# DL0815.net
KiCad netlist of a schematic drawn in EAGLE
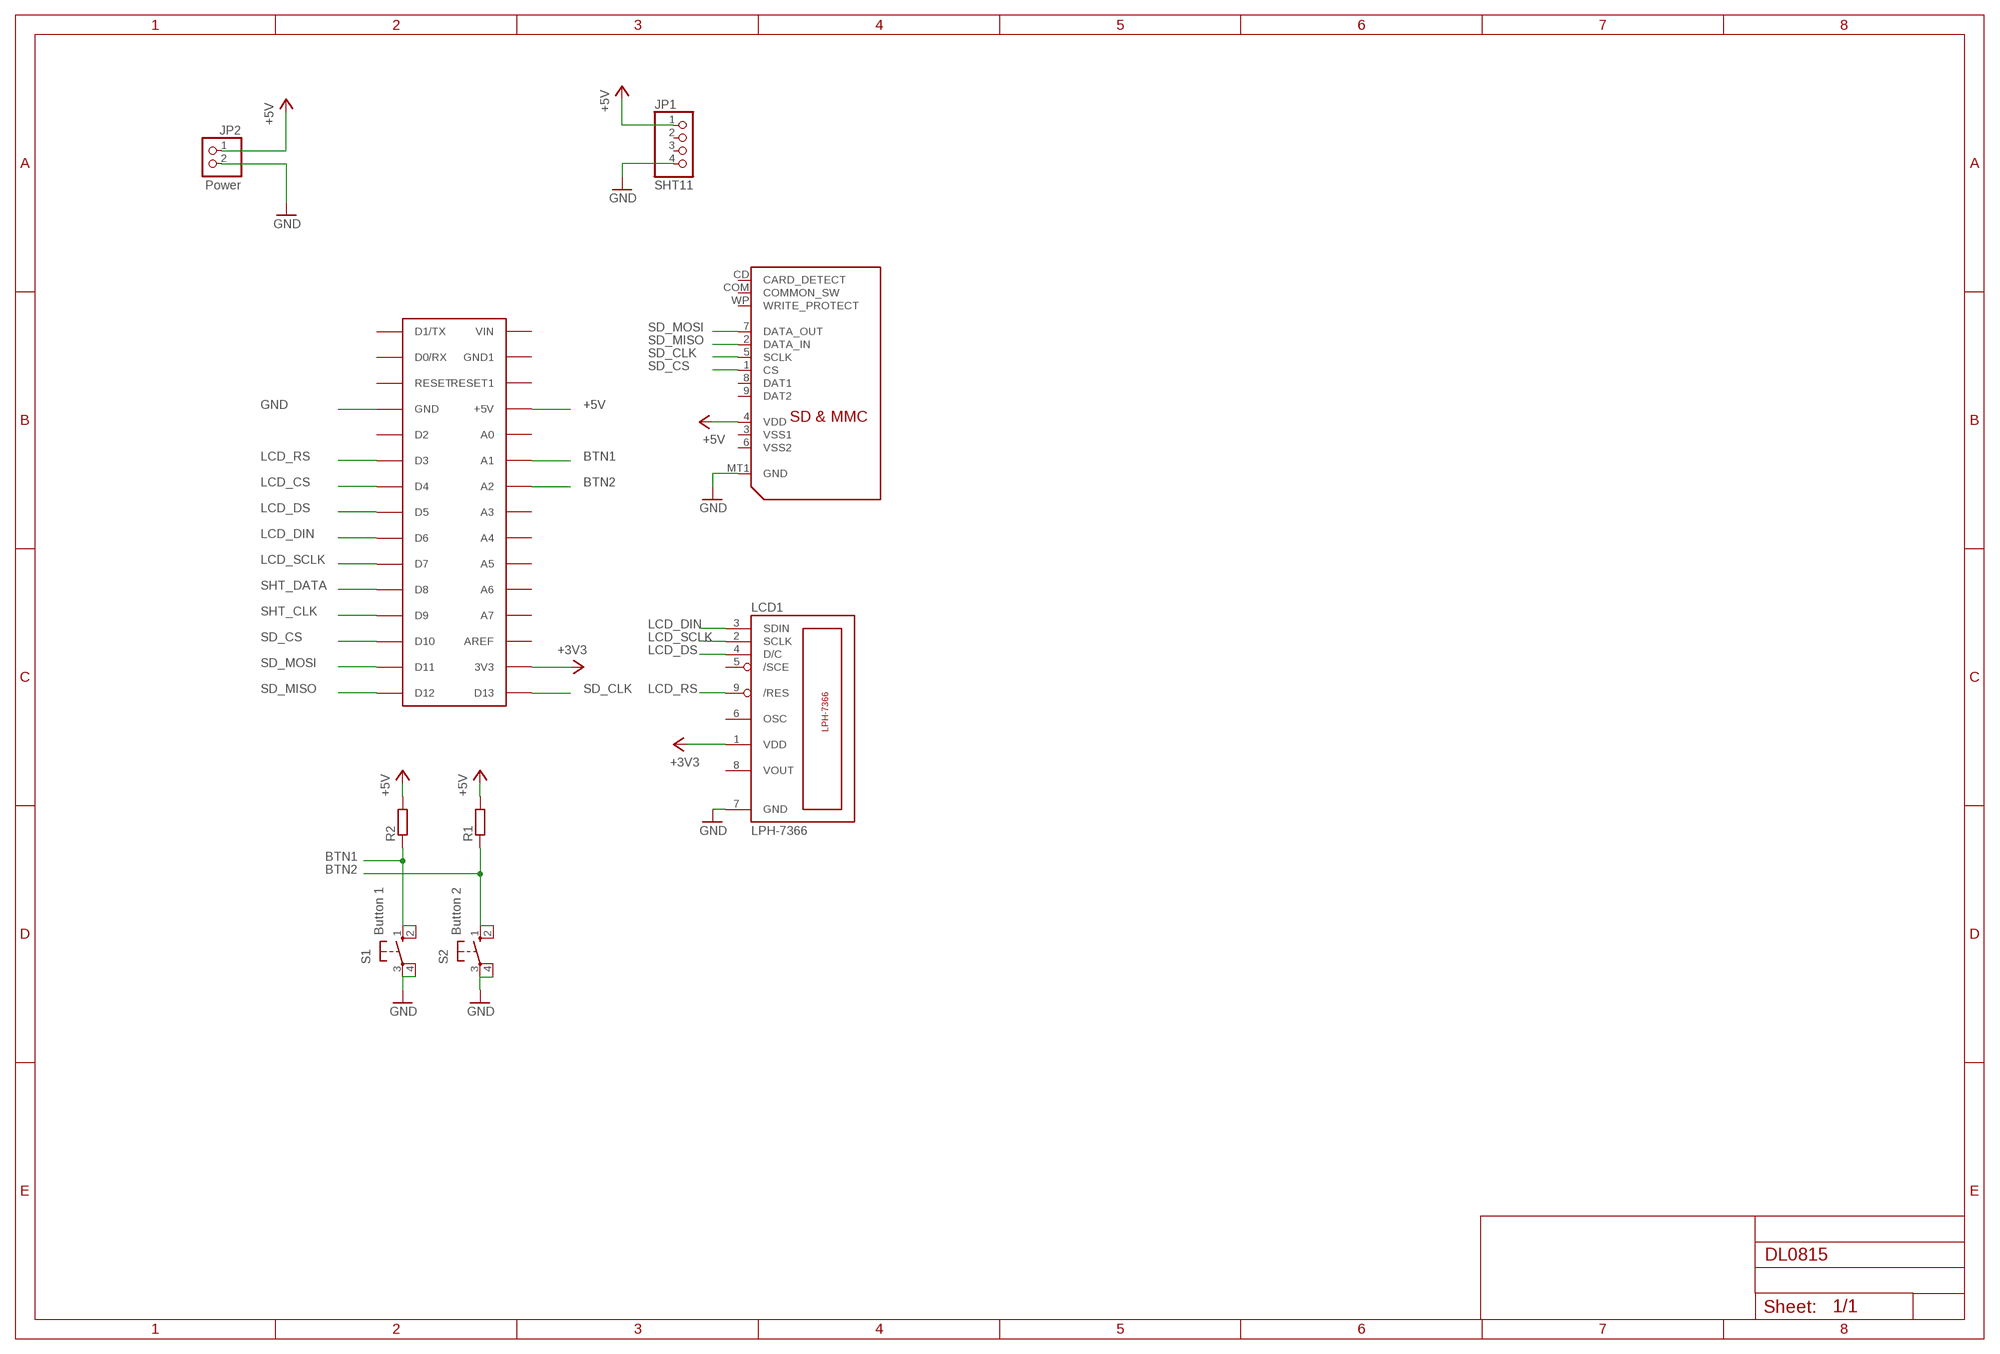
[diagram p0: schematic, sheet 1]

(export (version "E")
  (design (tool "Eeschema 10.0.6"))
  (components
    (comp (ref "JP1")
      (value "SHT11")
      (footprint "eagle-import:1X04")
      (libsource (lib "eagle-import") (part "PINHD-1X4"))
    )
    (comp (ref "JP2")
      (value "Power")
      (footprint "eagle-import:1X02")
      (libsource (lib "eagle-import") (part "PINHD-1X2"))
    )
    (comp (ref "LCD1")
      (value "LPH-7366")
      (footprint "eagle-import:LPH-7366")
      (libsource (lib "eagle-import") (part "LPH-7366"))
    )
    (comp (ref "R1")
      (value "R-EU_0204/7")
      (footprint "eagle-import:0204_7")
      (libsource (lib "eagle-import") (part "R-EU_0204/7"))
    )
    (comp (ref "R2")
      (value "R-EU_0204/7")
      (footprint "eagle-import:0204_7")
      (libsource (lib "eagle-import") (part "R-EU_0204/7"))
    )
    (comp (ref "S1")
      (value "Button 1")
      (footprint "eagle-import:B3F-40XX-ROUND")
      (libsource (lib "eagle-import") (part "40-XX-ROUND"))
    )
    (comp (ref "S2")
      (value "Button 2")
      (footprint "eagle-import:B3F-40XX-ROUND")
      (libsource (lib "eagle-import") (part "40-XX-ROUND"))
    )
    (comp (ref "U$1")
      (value "ARDUINONANO")
      (footprint "eagle-import:PDIP-32")
      (libsource (lib "eagle-import") (part "ARDUINONANO"))
    )
    (comp (ref "U$2")
      (value "SDMMC18650")
      (footprint "eagle-import:SDCARD")
      (libsource (lib "eagle-import") (part "SDMMC18650"))
    )
  )
  (nets
    (net (code "1") (name "+3V3") (class "Default")
      (node (ref "LCD1") (pin "1") (pinfunction "VDD_1") (pintype "power_in"))
      (node (ref "U$1") (pin "3V3") (pinfunction "3V3_3V3") (pintype "bidirectional"))
    )
    (net (code "2") (name "+5V") (class "Default")
      (node (ref "JP1") (pin "1") (pinfunction "1_1") (pintype "passive"))
      (node (ref "JP2") (pin "1") (pinfunction "1_1") (pintype "passive"))
      (node (ref "R1") (pin "2") (pinfunction "2_2") (pintype "passive"))
      (node (ref "R2") (pin "2") (pinfunction "2_2") (pintype "passive"))
      (node (ref "U$1") (pin "+5V") (pinfunction "+5V_+5V") (pintype "bidirectional"))
      (node (ref "U$2") (pin "4") (pinfunction "VDD_4") (pintype "power_in"))
    )
    (net (code "3") (name "/BTN1") (class "Default")
      (node (ref "R2") (pin "1") (pinfunction "1_1") (pintype "passive"))
      (node (ref "S1") (pin "1") (pinfunction "S_1") (pintype "passive"))
      (node (ref "S1") (pin "2") (pinfunction "S1_2") (pintype "passive"))
      (node (ref "U$1") (pin "A1") (pinfunction "A1_A1") (pintype "bidirectional"))
    )
    (net (code "4") (name "/BTN2") (class "Default")
      (node (ref "R1") (pin "1") (pinfunction "1_1") (pintype "passive"))
      (node (ref "S2") (pin "1") (pinfunction "S_1") (pintype "passive"))
      (node (ref "S2") (pin "2") (pinfunction "S1_2") (pintype "passive"))
      (node (ref "U$1") (pin "A2") (pinfunction "A2_A2") (pintype "bidirectional"))
    )
    (net (code "5") (name "/LCD_CS") (class "Default")
      (node (ref "U$1") (pin "D4") (pinfunction "D4_D4") (pintype "bidirectional"))
    )
    (net (code "6") (name "/LCD_DIN") (class "Default")
      (node (ref "LCD1") (pin "3") (pinfunction "SDIN_3") (pintype "input"))
      (node (ref "U$1") (pin "D6") (pinfunction "D6_D6") (pintype "bidirectional"))
    )
    (net (code "7") (name "/LCD_DS") (class "Default")
      (node (ref "LCD1") (pin "4") (pinfunction "D/C_4") (pintype "input"))
      (node (ref "U$1") (pin "D5") (pinfunction "D5_D5") (pintype "bidirectional"))
    )
    (net (code "8") (name "/LCD_RS") (class "Default")
      (node (ref "LCD1") (pin "9") (pinfunction "/RES_9") (pintype "input"))
      (node (ref "U$1") (pin "D3") (pinfunction "D3_D3") (pintype "bidirectional"))
    )
    (net (code "9") (name "/LCD_SCLK") (class "Default")
      (node (ref "LCD1") (pin "2") (pinfunction "SCLK_2") (pintype "input"))
      (node (ref "U$1") (pin "D7") (pinfunction "D7_D7") (pintype "bidirectional"))
    )
    (net (code "10") (name "/SD_CLK") (class "Default")
      (node (ref "U$1") (pin "D13") (pinfunction "D13_D13") (pintype "bidirectional"))
      (node (ref "U$2") (pin "5") (pinfunction "SCLK_5") (pintype "input"))
    )
    (net (code "11") (name "/SD_CS") (class "Default")
      (node (ref "U$1") (pin "D10") (pinfunction "D10_D10") (pintype "bidirectional"))
      (node (ref "U$2") (pin "1") (pinfunction "CS_1") (pintype "input"))
    )
    (net (code "12") (name "/SD_MISO") (class "Default")
      (node (ref "U$1") (pin "D12") (pinfunction "D12_D12") (pintype "bidirectional"))
      (node (ref "U$2") (pin "2") (pinfunction "DATA_IN_2") (pintype "input"))
    )
    (net (code "13") (name "/SD_MOSI") (class "Default")
      (node (ref "U$1") (pin "D11") (pinfunction "D11_D11") (pintype "bidirectional"))
      (node (ref "U$2") (pin "7") (pinfunction "DATA_OUT_7") (pintype "output"))
    )
    (net (code "14") (name "/SHT_CLK") (class "Default")
      (node (ref "U$1") (pin "D9") (pinfunction "D9_D9") (pintype "bidirectional"))
    )
    (net (code "15") (name "/SHT_DATA") (class "Default")
      (node (ref "U$1") (pin "D8") (pinfunction "D8_D8") (pintype "bidirectional"))
    )
    (net (code "16") (name "/VSS1") (class "Default")
      (node (ref "U$2") (pin "3") (pinfunction "VSS1_3") (pintype "power_in"))
    )
    (net (code "17") (name "/VSS2") (class "Default")
      (node (ref "U$2") (pin "6") (pinfunction "VSS2_6") (pintype "power_in"))
    )
    (net (code "18") (name "GND") (class "Default")
      (node (ref "JP1") (pin "4") (pinfunction "4_4") (pintype "passive"))
      (node (ref "JP2") (pin "2") (pinfunction "2_2") (pintype "passive"))
      (node (ref "LCD1") (pin "7") (pinfunction "GND_7") (pintype "power_in"))
      (node (ref "S1") (pin "3") (pinfunction "P_3") (pintype "passive"))
      (node (ref "S1") (pin "4") (pinfunction "P1_4") (pintype "passive"))
      (node (ref "S2") (pin "3") (pinfunction "P_3") (pintype "passive"))
      (node (ref "S2") (pin "4") (pinfunction "P1_4") (pintype "passive"))
      (node (ref "U$1") (pin "GND") (pinfunction "GND_GND") (pintype "bidirectional"))
      (node (ref "U$2") (pin "MT1") (pinfunction "GND_MT1") (pintype "power_in"))
    )
    (net (code "19") (name "unconnected-(JP1-Pad2)") (class "Default")
      (node (ref "JP1") (pin "2") (pinfunction "2_2") (pintype "passive"))
    )
    (net (code "20") (name "unconnected-(JP1-Pad3)") (class "Default")
      (node (ref "JP1") (pin "3") (pinfunction "3_3") (pintype "passive"))
    )
    (net (code "21") (name "unconnected-(LCD1-OSC-Pad6)") (class "Default")
      (node (ref "LCD1") (pin "6") (pinfunction "OSC_6") (pintype "passive"))
    )
    (net (code "22") (name "unconnected-(LCD1-VOUT-Pad8)") (class "Default")
      (node (ref "LCD1") (pin "8") (pinfunction "VOUT_8") (pintype "passive"))
    )
    (net (code "23") (name "unconnected-(LCD1-{slash}SCE-Pad5)") (class "Default")
      (node (ref "LCD1") (pin "5") (pinfunction "/SCE_5") (pintype "input"))
    )
    (net (code "24") (name "unconnected-(U$1-PadA0)") (class "Default")
      (node (ref "U$1") (pin "A0") (pinfunction "A0_A0") (pintype "bidirectional"))
    )
    (net (code "25") (name "unconnected-(U$1-PadA3)") (class "Default")
      (node (ref "U$1") (pin "A3") (pinfunction "A3_A3") (pintype "bidirectional"))
    )
    (net (code "26") (name "unconnected-(U$1-PadA4)") (class "Default")
      (node (ref "U$1") (pin "A4") (pinfunction "A4_A4") (pintype "bidirectional"))
    )
    (net (code "27") (name "unconnected-(U$1-PadA5)") (class "Default")
      (node (ref "U$1") (pin "A5") (pinfunction "A5_A5") (pintype "bidirectional"))
    )
    (net (code "28") (name "unconnected-(U$1-PadA6)") (class "Default")
      (node (ref "U$1") (pin "A6") (pinfunction "A6_A6") (pintype "bidirectional"))
    )
    (net (code "29") (name "unconnected-(U$1-PadA7)") (class "Default")
      (node (ref "U$1") (pin "A7") (pinfunction "A7_A7") (pintype "bidirectional"))
    )
    (net (code "30") (name "unconnected-(U$1-PadAREF)") (class "Default")
      (node (ref "U$1") (pin "AREF") (pinfunction "AREF_AREF") (pintype "bidirectional"))
    )
    (net (code "31") (name "unconnected-(U$1-PadD0{slash}RX)") (class "Default")
      (node (ref "U$1") (pin "D0/RX") (pinfunction "D0/RX_D0/RX") (pintype "bidirectional"))
    )
    (net (code "32") (name "unconnected-(U$1-PadD1{slash}TX)") (class "Default")
      (node (ref "U$1") (pin "D1/TX") (pinfunction "D1/TX_D1/TX") (pintype "bidirectional"))
    )
    (net (code "33") (name "unconnected-(U$1-PadD2)") (class "Default")
      (node (ref "U$1") (pin "D2") (pinfunction "D2_D2") (pintype "bidirectional"))
    )
    (net (code "34") (name "unconnected-(U$1-PadGND1)") (class "Default")
      (node (ref "U$1") (pin "GND1") (pinfunction "GND1_GND1") (pintype "bidirectional"))
    )
    (net (code "35") (name "unconnected-(U$1-PadRESET)") (class "Default")
      (node (ref "U$1") (pin "RESET") (pinfunction "RESET_RESET") (pintype "bidirectional"))
    )
    (net (code "36") (name "unconnected-(U$1-PadRESET1)") (class "Default")
      (node (ref "U$1") (pin "RESET1") (pinfunction "RESET1_RESET1") (pintype "bidirectional"))
    )
    (net (code "37") (name "unconnected-(U$1-PadVIN)") (class "Default")
      (node (ref "U$1") (pin "VIN") (pinfunction "VIN_VIN") (pintype "bidirectional"))
    )
    (net (code "38") (name "unconnected-(U$2-CARD_DETECT-PadCD)") (class "Default")
      (node (ref "U$2") (pin "CD") (pinfunction "CARD_DETECT_CD") (pintype "passive"))
    )
    (net (code "39") (name "unconnected-(U$2-COMMON_SW-PadCOM)") (class "Default")
      (node (ref "U$2") (pin "COM") (pinfunction "COMMON_SW_COM") (pintype "passive"))
    )
    (net (code "40") (name "unconnected-(U$2-DAT1-Pad8)") (class "Default")
      (node (ref "U$2") (pin "8") (pinfunction "DAT1_8") (pintype "bidirectional"))
    )
    (net (code "41") (name "unconnected-(U$2-DAT2-Pad9)") (class "Default")
      (node (ref "U$2") (pin "9") (pinfunction "DAT2_9") (pintype "bidirectional"))
    )
    (net (code "42") (name "unconnected-(U$2-WRITE_PROTECT-PadWP)") (class "Default")
      (node (ref "U$2") (pin "WP") (pinfunction "WRITE_PROTECT_WP") (pintype "passive"))
    )
  )
)
